# RV8523-RTC-Breakout_v10.net
KiCad netlist of a schematic drawn in EAGLE
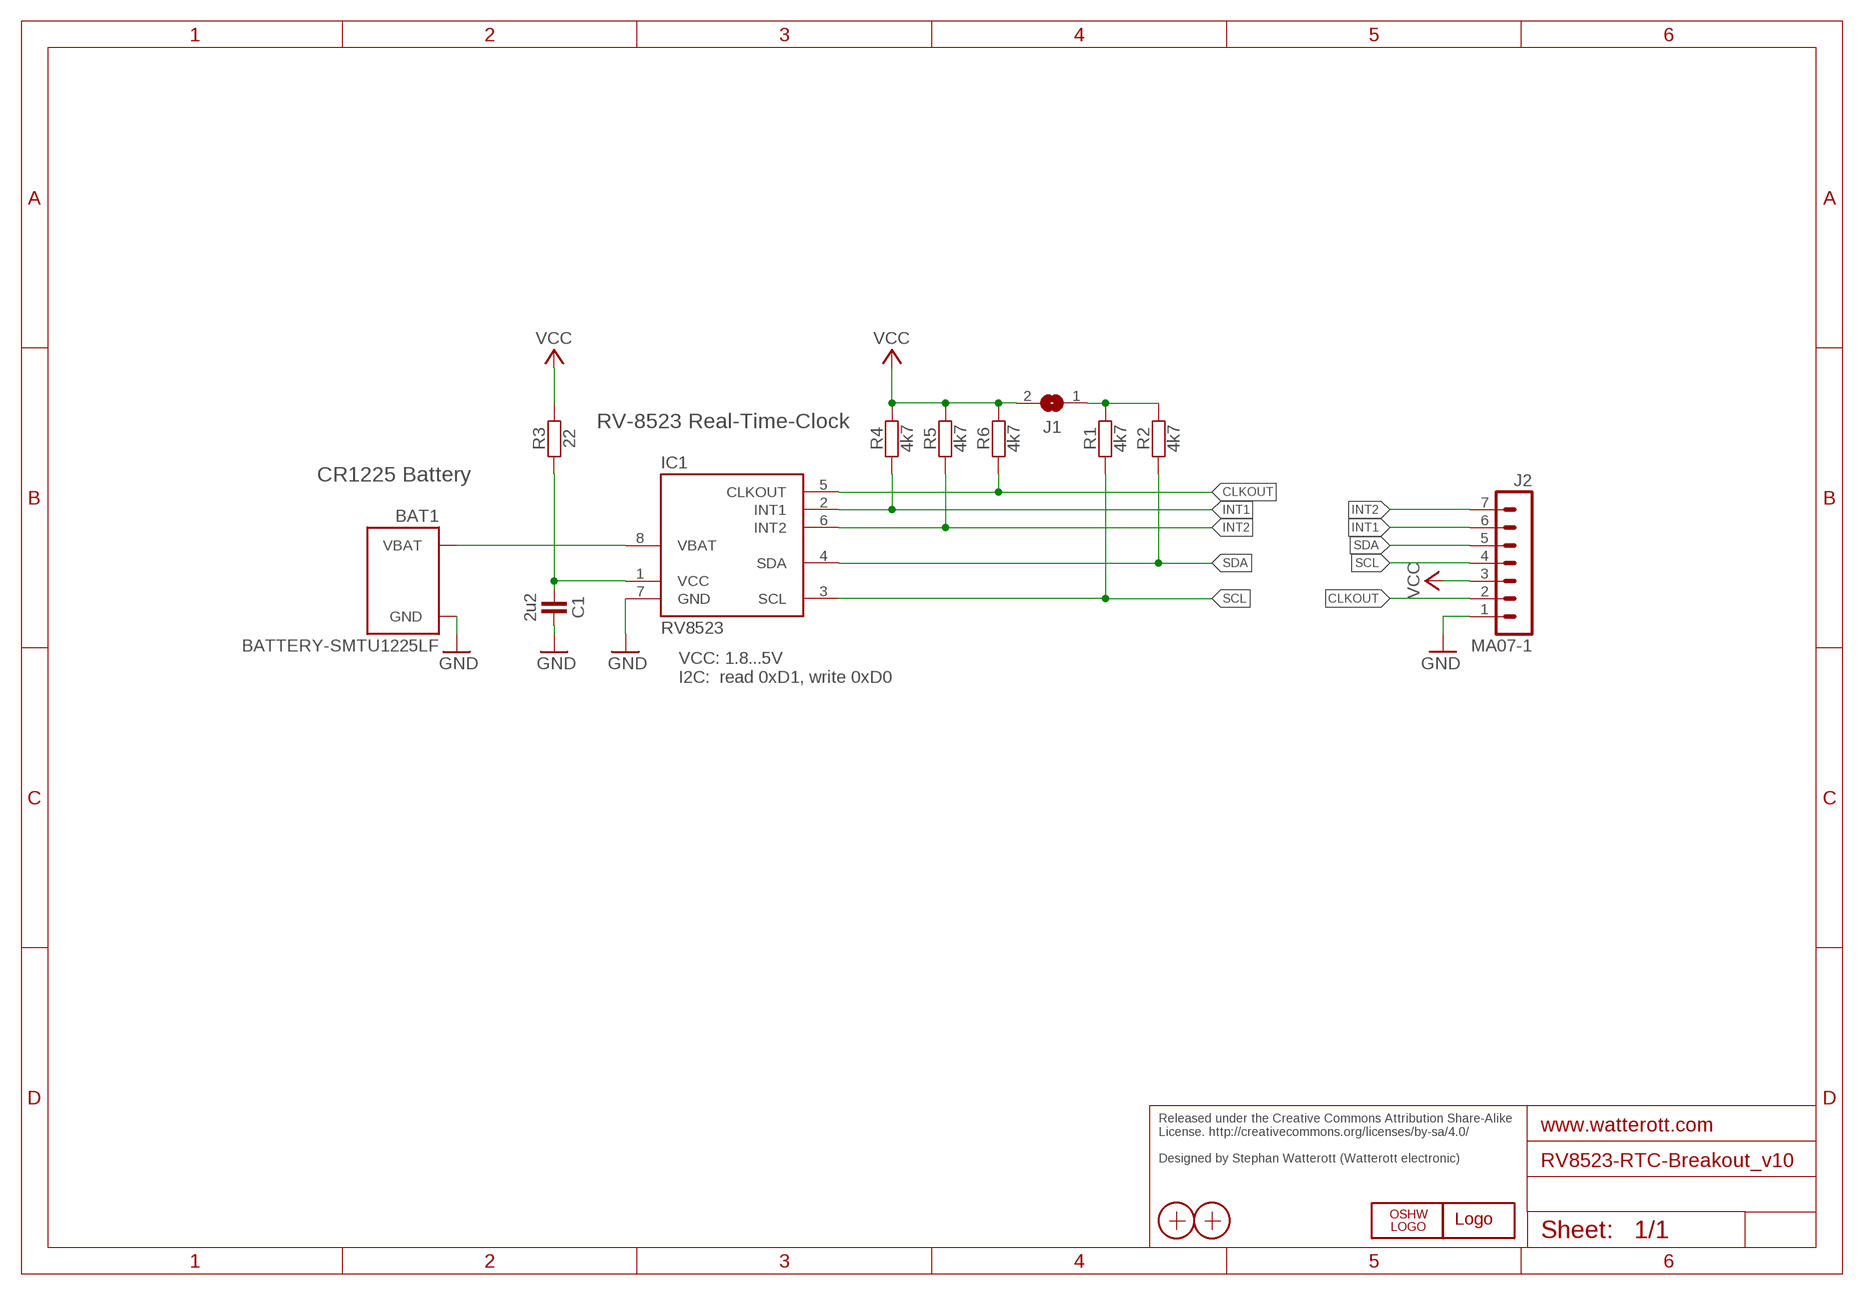
[diagram p0: schematic, sheet 1]

(export (version "E")
  (design (tool "Eeschema 10.0.6"))
  (components
    (comp (ref "BAT1")
      (value "BATTERY-SMTU1225LF")
      (footprint "eagle-import:BAT-SMTU1225LF")
      (libsource (lib "eagle-import") (part "BATTERY-SMTU1225LF"))
    )
    (comp (ref "C1")
      (value "2u2")
      (footprint "eagle-import:R0603")
      (libsource (lib "eagle-import") (part "CAPACITOR-C0603"))
    )
    (comp (ref "IC1")
      (value "RV8523")
      (footprint "eagle-import:RTC-C3")
      (libsource (lib "eagle-import") (part "RV8523-C3"))
    )
    (comp (ref "J1")
      (value "JUMPER2")
      (footprint "eagle-import:JUMPER2")
      (libsource (lib "eagle-import") (part "JUMPER2"))
    )
    (comp (ref "J2")
      (value "MA07-1")
      (footprint "eagle-import:MA07-1")
      (libsource (lib "eagle-import") (part "MA07-1"))
    )
    (comp (ref "LOGO1")
      (value "LOGO-S_PLACE_M")
      (footprint "eagle-import:SPARK_TPLACE_M")
      (libsource (lib "eagle-import") (part "LOGO-S_PLACE_M"))
    )
    (comp (ref "LOGO2")
      (value "OSHW_LOGOX0070")
      (footprint "eagle-import:OSHW_6X70")
      (libsource (lib "eagle-import") (part "OSHW_LOGOX0070"))
    )
    (comp (ref "R1")
      (value "4k7")
      (footprint "eagle-import:R0603")
      (libsource (lib "eagle-import") (part "RESISTOR-R0603"))
    )
    (comp (ref "R2")
      (value "4k7")
      (footprint "eagle-import:R0603")
      (libsource (lib "eagle-import") (part "RESISTOR-R0603"))
    )
    (comp (ref "R3")
      (value "22")
      (footprint "eagle-import:R0603")
      (libsource (lib "eagle-import") (part "RESISTOR-R0603"))
    )
    (comp (ref "R4")
      (value "4k7")
      (footprint "eagle-import:R0603")
      (libsource (lib "eagle-import") (part "RESISTOR-R0603"))
    )
    (comp (ref "R5")
      (value "4k7")
      (footprint "eagle-import:R0603")
      (libsource (lib "eagle-import") (part "RESISTOR-R0603"))
    )
    (comp (ref "R6")
      (value "4k7")
      (footprint "eagle-import:R0603")
      (libsource (lib "eagle-import") (part "RESISTOR-R0603"))
    )
    (comp (ref "X1")
      (value "PASSER-07")
      (footprint "eagle-import:PASSER_07MM")
      (libsource (lib "eagle-import") (part "PASSER-07"))
    )
    (comp (ref "X2")
      (value "PASSER-07")
      (footprint "eagle-import:PASSER_07MM")
      (libsource (lib "eagle-import") (part "PASSER-07"))
    )
  )
  (nets
    (net (code "1") (name "CLKOUT") (class "Default")
      (node (ref "IC1") (pin "5") (pinfunction "CLKOUT_5") (pintype "bidirectional"))
      (node (ref "J2") (pin "2") (pinfunction "2_2") (pintype "passive"))
      (node (ref "R6") (pin "1") (pinfunction "1_1") (pintype "passive"))
    )
    (net (code "2") (name "GND") (class "Default")
      (node (ref "BAT1") (pin "-") (pinfunction "GND_-") (pintype "passive"))
      (node (ref "C1") (pin "2") (pinfunction "2_2") (pintype "passive"))
      (node (ref "IC1") (pin "7") (pinfunction "GND_7") (pintype "power_in"))
      (node (ref "J2") (pin "1") (pinfunction "1_1") (pintype "passive"))
    )
    (net (code "3") (name "INT1") (class "Default")
      (node (ref "IC1") (pin "2") (pinfunction "INT1_2") (pintype "bidirectional"))
      (node (ref "J2") (pin "6") (pinfunction "6_6") (pintype "passive"))
      (node (ref "R4") (pin "1") (pinfunction "1_1") (pintype "passive"))
    )
    (net (code "4") (name "INT2") (class "Default")
      (node (ref "IC1") (pin "6") (pinfunction "INT2_6") (pintype "bidirectional"))
      (node (ref "J2") (pin "7") (pinfunction "7_7") (pintype "passive"))
      (node (ref "R5") (pin "1") (pinfunction "1_1") (pintype "passive"))
    )
    (net (code "5") (name "Net-(BAT1-VBAT)") (class "Default")
      (node (ref "BAT1") (pin "+") (pinfunction "VBAT_+") (pintype "passive"))
      (node (ref "IC1") (pin "8") (pinfunction "VBAT_8") (pintype "power_in"))
    )
    (net (code "6") (name "Net-(IC1-VCC)") (class "Default")
      (node (ref "C1") (pin "1") (pinfunction "1_1") (pintype "passive"))
      (node (ref "IC1") (pin "1") (pinfunction "VCC_1") (pintype "power_in"))
      (node (ref "R3") (pin "1") (pinfunction "1_1") (pintype "passive"))
    )
    (net (code "7") (name "Net-(J1-Pad1)") (class "Default")
      (node (ref "J1") (pin "1") (pinfunction "1_1") (pintype "passive"))
      (node (ref "R1") (pin "2") (pinfunction "2_2") (pintype "passive"))
      (node (ref "R2") (pin "2") (pinfunction "2_2") (pintype "passive"))
    )
    (net (code "8") (name "SCL") (class "Default")
      (node (ref "IC1") (pin "3") (pinfunction "SCL_3") (pintype "bidirectional"))
      (node (ref "J2") (pin "4") (pinfunction "4_4") (pintype "passive"))
      (node (ref "R1") (pin "1") (pinfunction "1_1") (pintype "passive"))
    )
    (net (code "9") (name "SDA") (class "Default")
      (node (ref "IC1") (pin "4") (pinfunction "SDA_4") (pintype "bidirectional"))
      (node (ref "J2") (pin "5") (pinfunction "5_5") (pintype "passive"))
      (node (ref "R2") (pin "1") (pinfunction "1_1") (pintype "passive"))
    )
    (net (code "10") (name "VCC") (class "Default")
      (node (ref "J1") (pin "2") (pinfunction "2_2") (pintype "passive"))
      (node (ref "J2") (pin "3") (pinfunction "3_3") (pintype "passive"))
      (node (ref "R3") (pin "2") (pinfunction "2_2") (pintype "passive"))
      (node (ref "R4") (pin "2") (pinfunction "2_2") (pintype "passive"))
      (node (ref "R5") (pin "2") (pinfunction "2_2") (pintype "passive"))
      (node (ref "R6") (pin "2") (pinfunction "2_2") (pintype "passive"))
    )
  )
)
